# output_amp_w_gp.net
KiCad netlist of a schematic drawn in EAGLE
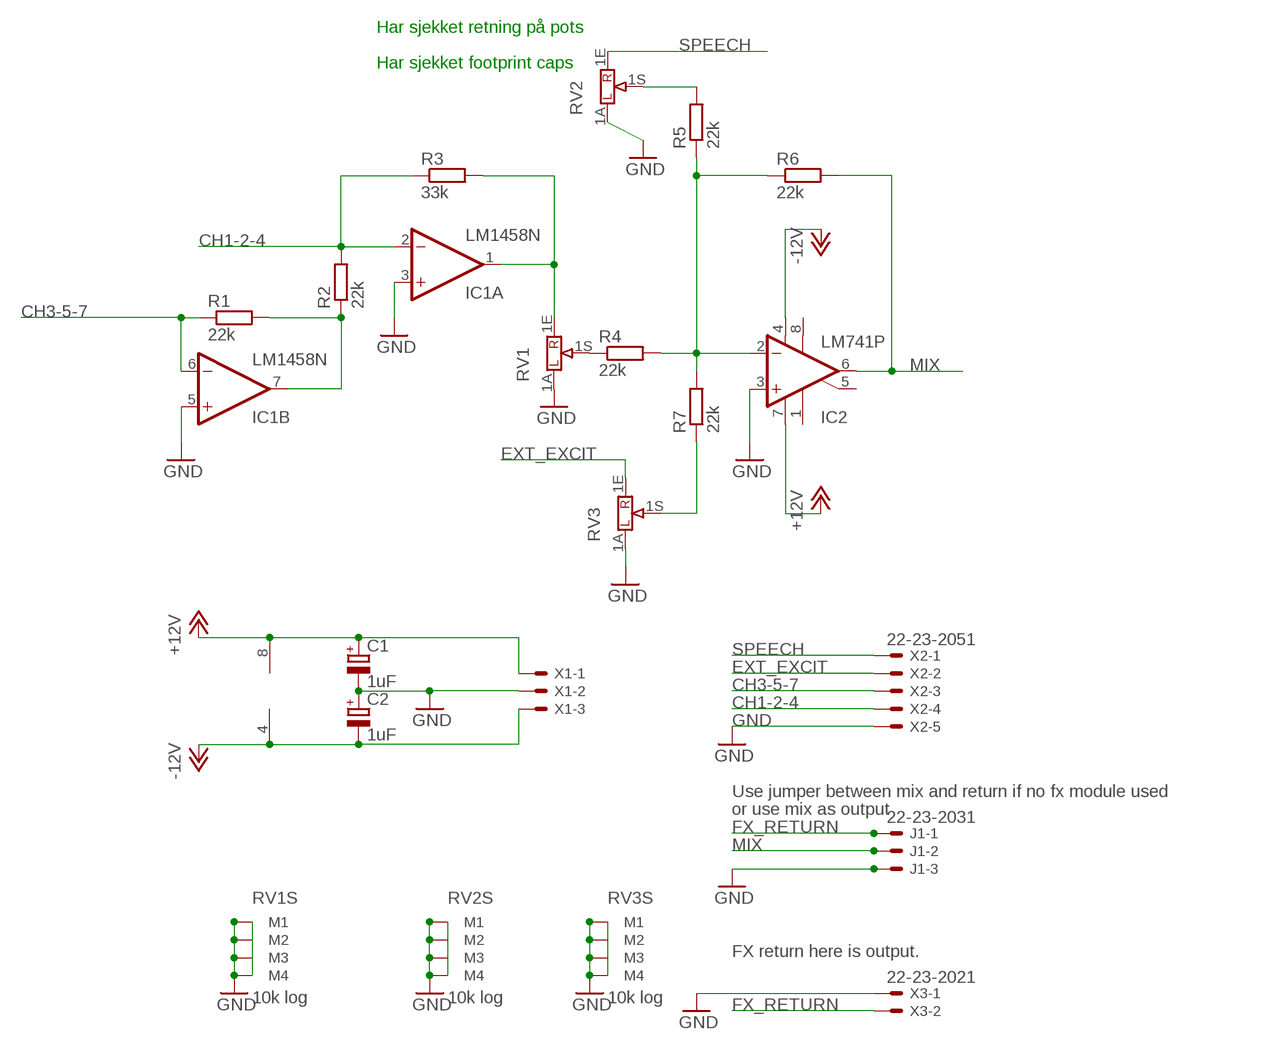
[diagram p0: schematic, sheet 1]

(export (version "E")
  (design (tool "Eeschema 10.0.6"))
  (components
    (comp (ref "C1")
      (value "1uF")
      (footprint "eagle-import:E2,5-5")
      (libsource (lib "eagle-import") (part "CPOL-EUE2.5-5"))
    )
    (comp (ref "C2")
      (value "1uF")
      (footprint "eagle-import:E2,5-5")
      (libsource (lib "eagle-import") (part "CPOL-EUE2.5-5"))
    )
    (comp (ref "IC1")
      (value "LM1458N")
      (footprint "eagle-import:DIL08")
      (libsource (lib "eagle-import") (part "1458NLM"))
    )
    (comp (ref "IC2")
      (value "LM741P")
      (footprint "eagle-import:DIL08")
      (libsource (lib "eagle-import") (part "741PLM"))
    )
    (comp (ref "J1")
      (value "22-23-2031")
      (footprint "eagle-import:22-23-2031")
      (fields (field (name "MF") "MOLEX"))
      (libsource (lib "eagle-import") (part "22-23-2031"))
    )
    (comp (ref "R1")
      (value "22k")
      (footprint "eagle-import:0207_7")
      (libsource (lib "eagle-import") (part "R-EU_0207/7"))
    )
    (comp (ref "R2")
      (value "22k")
      (footprint "eagle-import:0207_7")
      (libsource (lib "eagle-import") (part "R-EU_0207/7"))
    )
    (comp (ref "R3")
      (value "33k")
      (footprint "eagle-import:0207_7")
      (libsource (lib "eagle-import") (part "R-EU_0207/7"))
    )
    (comp (ref "R4")
      (value "22k")
      (footprint "eagle-import:0207_7")
      (libsource (lib "eagle-import") (part "R-EU_0207/7"))
    )
    (comp (ref "R5")
      (value "22k")
      (footprint "eagle-import:0207_7")
      (libsource (lib "eagle-import") (part "R-EU_0207/7"))
    )
    (comp (ref "R6")
      (value "22k")
      (footprint "eagle-import:0207_7")
      (libsource (lib "eagle-import") (part "R-EU_0207/7"))
    )
    (comp (ref "R7")
      (value "22k")
      (footprint "eagle-import:0207_7")
      (libsource (lib "eagle-import") (part "R-EU_0207/7"))
    )
    (comp (ref "RV1")
      (value "10k log")
      (footprint "eagle-import:POT16_W_BRACKET")
      (libsource (lib "eagle-import") (part "POT16_W_BRACKET{dblquote}{dblquote}"))
    )
    (comp (ref "RV2")
      (value "10k log")
      (footprint "eagle-import:POT16_W_BRACKET")
      (libsource (lib "eagle-import") (part "POT16_W_BRACKET{dblquote}{dblquote}"))
    )
    (comp (ref "RV3")
      (value "10k log")
      (footprint "eagle-import:POT16_W_BRACKET")
      (libsource (lib "eagle-import") (part "POT16_W_BRACKET{dblquote}{dblquote}"))
    )
    (comp (ref "X1")
      (value "KK-156-3")
      (footprint "eagle-import:KK-156-3")
      (libsource (lib "eagle-import") (part "KK-156-3"))
    )
    (comp (ref "X2")
      (value "22-23-2051")
      (footprint "eagle-import:22-23-2051")
      (fields (field (name "MF") "MOLEX"))
      (libsource (lib "eagle-import") (part "22-23-2051"))
    )
    (comp (ref "X3")
      (value "22-23-2021")
      (footprint "eagle-import:22-23-2021")
      (fields (field (name "MF") "MOLEX"))
      (libsource (lib "eagle-import") (part "22-23-2021"))
    )
  )
  (nets
    (net (code "1") (name "+12V") (class "Default")
      (node (ref "C1") (pin "+") (pinfunction "+_+") (pintype "passive"))
      (node (ref "IC1") (pin "8") (pinfunction "V+_8") (pintype "power_in"))
      (node (ref "IC2") (pin "7") (pinfunction "V+_7") (pintype "power_in"))
      (node (ref "X1") (pin "1") (pinfunction "S_1") (pintype "passive"))
    )
    (net (code "2") (name "-12V") (class "Default")
      (node (ref "C2") (pin "-") (pinfunction "-_-") (pintype "passive"))
      (node (ref "IC1") (pin "4") (pinfunction "V-_4") (pintype "power_in"))
      (node (ref "IC2") (pin "4") (pinfunction "V-_4") (pintype "power_in"))
      (node (ref "X1") (pin "3") (pinfunction "S_3") (pintype "passive"))
    )
    (net (code "3") (name "/CH1-2-4") (class "Default")
      (node (ref "IC1") (pin "2") (pinfunction "-IN_2") (pintype "input"))
      (node (ref "R2") (pin "2") (pinfunction "2_2") (pintype "passive"))
      (node (ref "R3") (pin "1") (pinfunction "1_1") (pintype "passive"))
      (node (ref "X2") (pin "4") (pinfunction "S_4") (pintype "passive"))
    )
    (net (code "4") (name "/CH3-5-7") (class "Default")
      (node (ref "IC1") (pin "6") (pinfunction "-IN_6") (pintype "input"))
      (node (ref "R1") (pin "1") (pinfunction "1_1") (pintype "passive"))
      (node (ref "X2") (pin "3") (pinfunction "S_3") (pintype "passive"))
    )
    (net (code "5") (name "/EXT_EXCIT") (class "Default")
      (node (ref "RV3") (pin "1E") (pinfunction "1E_1E") (pintype "passive"))
      (node (ref "X2") (pin "2") (pinfunction "S_2") (pintype "passive"))
    )
    (net (code "6") (name "/FX_RETURN") (class "Default")
      (node (ref "J1") (pin "1") (pinfunction "S_1") (pintype "passive"))
      (node (ref "X3") (pin "2") (pinfunction "S_2") (pintype "passive"))
    )
    (net (code "7") (name "/MIX") (class "Default")
      (node (ref "IC2") (pin "6") (pinfunction "OUT_6") (pintype "output"))
      (node (ref "J1") (pin "2") (pinfunction "S_2") (pintype "passive"))
      (node (ref "R6") (pin "2") (pinfunction "2_2") (pintype "passive"))
    )
    (net (code "8") (name "/SPEECH") (class "Default")
      (node (ref "RV2") (pin "1E") (pinfunction "1E_1E") (pintype "passive"))
      (node (ref "X2") (pin "1") (pinfunction "S_1") (pintype "passive"))
    )
    (net (code "9") (name "GND") (class "Default")
      (node (ref "C1") (pin "-") (pinfunction "-_-") (pintype "passive"))
      (node (ref "C2") (pin "+") (pinfunction "+_+") (pintype "passive"))
      (node (ref "IC1") (pin "3") (pinfunction "+IN_3") (pintype "input"))
      (node (ref "IC1") (pin "5") (pinfunction "+IN_5") (pintype "input"))
      (node (ref "IC2") (pin "3") (pinfunction "+IN_3") (pintype "input"))
      (node (ref "J1") (pin "3") (pinfunction "S_3") (pintype "passive"))
      (node (ref "RV1") (pin "1A") (pinfunction "1A_1A") (pintype "passive"))
      (node (ref "RV1") (pin "M1") (pinfunction "M1_M1") (pintype "passive"))
      (node (ref "RV1") (pin "M2") (pinfunction "M2_M2") (pintype "passive"))
      (node (ref "RV1") (pin "M3") (pinfunction "M3_M3") (pintype "passive"))
      (node (ref "RV1") (pin "M4") (pinfunction "M4_M4") (pintype "passive"))
      (node (ref "RV2") (pin "1A") (pinfunction "1A_1A") (pintype "passive"))
      (node (ref "RV2") (pin "M1") (pinfunction "M1_M1") (pintype "passive"))
      (node (ref "RV2") (pin "M2") (pinfunction "M2_M2") (pintype "passive"))
      (node (ref "RV2") (pin "M3") (pinfunction "M3_M3") (pintype "passive"))
      (node (ref "RV2") (pin "M4") (pinfunction "M4_M4") (pintype "passive"))
      (node (ref "RV3") (pin "1A") (pinfunction "1A_1A") (pintype "passive"))
      (node (ref "RV3") (pin "M1") (pinfunction "M1_M1") (pintype "passive"))
      (node (ref "RV3") (pin "M2") (pinfunction "M2_M2") (pintype "passive"))
      (node (ref "RV3") (pin "M3") (pinfunction "M3_M3") (pintype "passive"))
      (node (ref "RV3") (pin "M4") (pinfunction "M4_M4") (pintype "passive"))
      (node (ref "X1") (pin "2") (pinfunction "S_2") (pintype "passive"))
      (node (ref "X2") (pin "5") (pinfunction "S_5") (pintype "passive"))
      (node (ref "X3") (pin "1") (pinfunction "S_1") (pintype "passive"))
    )
    (net (code "10") (name "Net-(IC1A-OUT)") (class "Default")
      (node (ref "IC1") (pin "1") (pinfunction "OUT_1") (pintype "output"))
      (node (ref "R3") (pin "2") (pinfunction "2_2") (pintype "passive"))
      (node (ref "RV1") (pin "1E") (pinfunction "1E_1E") (pintype "passive"))
    )
    (net (code "11") (name "Net-(IC1B-OUT)") (class "Default")
      (node (ref "IC1") (pin "7") (pinfunction "OUT_7") (pintype "output"))
      (node (ref "R1") (pin "2") (pinfunction "2_2") (pintype "passive"))
      (node (ref "R2") (pin "1") (pinfunction "1_1") (pintype "passive"))
    )
    (net (code "12") (name "Net-(IC2--IN)") (class "Default")
      (node (ref "IC2") (pin "2") (pinfunction "-IN_2") (pintype "input"))
      (node (ref "R4") (pin "2") (pinfunction "2_2") (pintype "passive"))
      (node (ref "R5") (pin "1") (pinfunction "1_1") (pintype "passive"))
      (node (ref "R6") (pin "1") (pinfunction "1_1") (pintype "passive"))
      (node (ref "R7") (pin "2") (pinfunction "2_2") (pintype "passive"))
    )
    (net (code "13") (name "Net-(R4-Pad1)") (class "Default")
      (node (ref "R4") (pin "1") (pinfunction "1_1") (pintype "passive"))
      (node (ref "RV1") (pin "1S") (pinfunction "1S_1S") (pintype "passive"))
    )
    (net (code "14") (name "Net-(R5-Pad2)") (class "Default")
      (node (ref "R5") (pin "2") (pinfunction "2_2") (pintype "passive"))
      (node (ref "RV2") (pin "1S") (pinfunction "1S_1S") (pintype "passive"))
    )
    (net (code "15") (name "Net-(R7-Pad1)") (class "Default")
      (node (ref "R7") (pin "1") (pinfunction "1_1") (pintype "passive"))
      (node (ref "RV3") (pin "1S") (pinfunction "1S_1S") (pintype "passive"))
    )
    (net (code "16") (name "unconnected-(IC2-ON1-Pad1)") (class "Default")
      (node (ref "IC2") (pin "1") (pinfunction "ON1_1") (pintype "passive"))
    )
    (net (code "17") (name "unconnected-(IC2-ON2-Pad5)") (class "Default")
      (node (ref "IC2") (pin "5") (pinfunction "ON2_5") (pintype "passive"))
    )
    (net (code "18") (name "unconnected-(IC2-OPT-Pad8)") (class "Default")
      (node (ref "IC2") (pin "8") (pinfunction "OPT_8") (pintype "passive"))
    )
  )
)
